# Power.net
KiCad netlist of a schematic drawn in Altium Designer
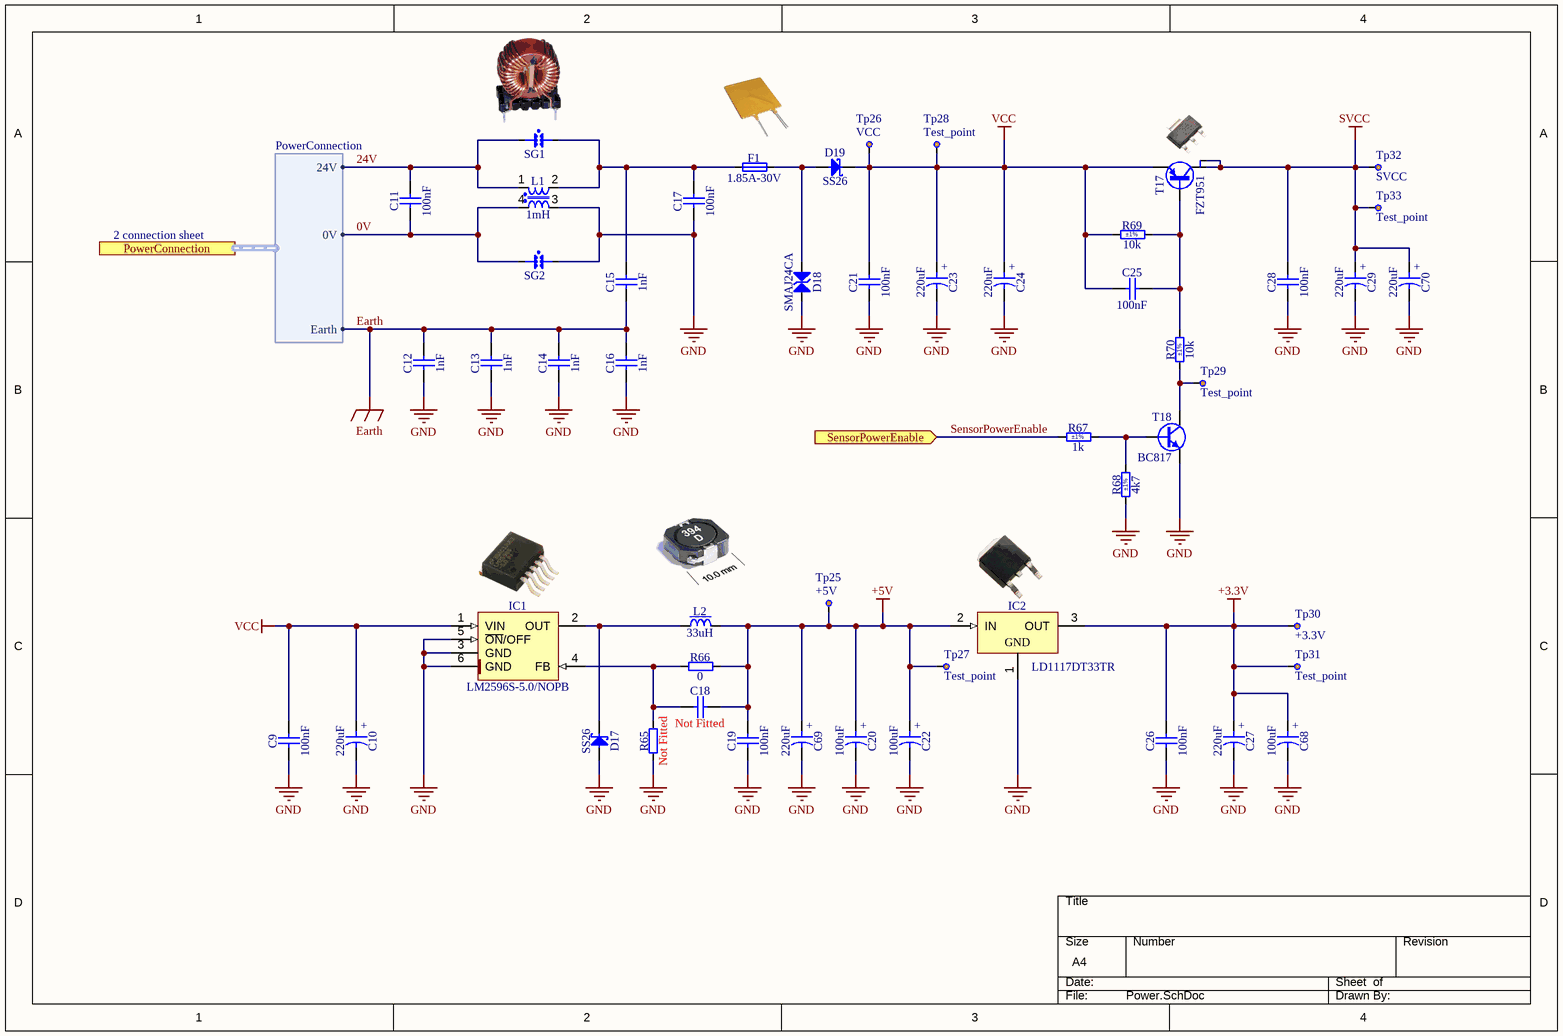
[diagram p0: Power.SchDoc]

(export (version "E")
  (design (tool "Eeschema 10.0.6"))
  (components
    (comp (ref "C9")
      (value "100nF")
      (footprint "CAPC3216X140N")
      (description "Non-polarised capacitor")
      (fields
        (field (name "PART NUMBER") "CC1206_100NF_100V_10%_X7R")
        (field (name "VOLTAGE") "100V")
        (field (name "AUTHOR") "CERN DEM JLC")
      )
      (libsource (lib "Capacitors") (part "Capacitor - non polarized"))
    )
    (comp (ref "C10")
      (value "220uF")
      (footprint "CAPAE830X1020N")
      (description "Polarised capacitor")
      (fields
        (field (name "PART NUMBER") "CAE830-1020_220UF_50V_20%")
        (field (name "VOLTAGE") "50V")
        (field (name "AUTHOR") "CERN DEM BC")
      )
      (libsource (lib "Capacitors") (part "Capacitor - polarized"))
    )
    (comp (ref "C11")
      (value "100nF")
      (footprint "CAPC3216X140N")
      (description "Non-polarised capacitor")
      (fields
        (field (name "PART NUMBER") "CC1206_100NF_100V_10%_X7R")
        (field (name "VOLTAGE") "100V")
        (field (name "AUTHOR") "CERN DEM JLC")
      )
      (libsource (lib "Capacitors") (part "Capacitor - non polarized"))
    )
    (comp (ref "C12")
      (value "1nF")
      (footprint "CAPC3216X94N")
      (description "Non-polarised capacitor")
      (fields
        (field (name "PART NUMBER") "CC1206_1NF_200V_10%_X7R")
        (field (name "VOLTAGE") "200V")
        (field (name "AUTHOR") "CERN DEM JLC")
      )
      (libsource (lib "Capacitors") (part "Capacitor - non polarized"))
    )
    (comp (ref "C13")
      (value "1nF")
      (footprint "CAPC3216X94N")
      (description "Non-polarised capacitor")
      (fields
        (field (name "PART NUMBER") "CC1206_1NF_200V_10%_X7R")
        (field (name "VOLTAGE") "200V")
        (field (name "AUTHOR") "CERN DEM JLC")
      )
      (libsource (lib "Capacitors") (part "Capacitor - non polarized"))
    )
    (comp (ref "C14")
      (value "1nF")
      (footprint "CAPC3216X94N")
      (description "Non-polarised capacitor")
      (fields
        (field (name "PART NUMBER") "CC1206_1NF_200V_10%_X7R")
        (field (name "VOLTAGE") "200V")
        (field (name "AUTHOR") "CERN DEM JLC")
      )
      (libsource (lib "Capacitors") (part "Capacitor - non polarized"))
    )
    (comp (ref "C15")
      (value "1nF")
      (footprint "CAPC3216X94N")
      (description "Non-polarised capacitor")
      (fields
        (field (name "PART NUMBER") "CC1206_1NF_200V_10%_X7R")
        (field (name "VOLTAGE") "200V")
        (field (name "AUTHOR") "CERN DEM JLC")
      )
      (libsource (lib "Capacitors") (part "Capacitor - non polarized"))
    )
    (comp (ref "C16")
      (value "1nF")
      (footprint "CAPC3216X94N")
      (description "Non-polarised capacitor")
      (fields
        (field (name "PART NUMBER") "CC1206_1NF_200V_10%_X7R")
        (field (name "VOLTAGE") "200V")
        (field (name "AUTHOR") "CERN DEM JLC")
      )
      (libsource (lib "Capacitors") (part "Capacitor - non polarized"))
    )
    (comp (ref "C17")
      (value "100nF")
      (footprint "CAPC3216X140N")
      (description "Non-polarised capacitor")
      (fields
        (field (name "PART NUMBER") "CC1206_100NF_100V_10%_X7R")
        (field (name "VOLTAGE") "100V")
        (field (name "AUTHOR") "CERN DEM JLC")
      )
      (libsource (lib "Capacitors") (part "Capacitor - non polarized"))
    )
    (comp (ref "C18")
      (value "Not Fitted")
      (footprint "CAPC2012X135N")
      (description "Non-polarised capacitor")
      (fields
        (field (name "PART NUMBER") "CC0805_NO-VALUE")
        (field (name "MANUFACTURER") "Undefined")
        (field (name "AUTHOR") "CERN DEM JLC")
      )
      (libsource (lib "Capacitors") (part "Capacitor - non polarized"))
    )
    (comp (ref "C19")
      (value "100nF")
      (footprint "CAPC1608X87N")
      (description "Non-polarised capacitor")
      (fields
        (field (name "PART NUMBER") "CC0603_100NF_50V_10%_X7R")
        (field (name "VOLTAGE") "50V")
        (field (name "AUTHOR") "CERN DEM JLC")
      )
      (libsource (lib "Capacitors") (part "Capacitor - non polarized"))
    )
    (comp (ref "C20")
      (value "100uF")
      (footprint "CAPMP6032X280N")
      (description "Polarised capacitor")
      (fields
        (field (name "PART NUMBER") "CTE6032-28_100UF_16V_10%")
        (field (name "VOLTAGE") "16V")
        (field (name "AUTHOR") "CERN DEM JLC")
      )
      (libsource (lib "Capacitors") (part "Capacitor - polarized"))
    )
    (comp (ref "C21")
      (value "100nF")
      (footprint "CAPC3216X140N")
      (description "Non-polarised capacitor")
      (fields
        (field (name "PART NUMBER") "CC1206_100NF_100V_10%_X7R")
        (field (name "VOLTAGE") "100V")
        (field (name "AUTHOR") "CERN DEM JLC")
      )
      (libsource (lib "Capacitors") (part "Capacitor - non polarized"))
    )
    (comp (ref "C22")
      (value "100uF")
      (footprint "CAPMP6032X280N")
      (description "Polarised capacitor")
      (fields
        (field (name "PART NUMBER") "CTE6032-28_100UF_16V_10%")
        (field (name "VOLTAGE") "16V")
        (field (name "AUTHOR") "CERN DEM JLC")
      )
      (libsource (lib "Capacitors") (part "Capacitor - polarized"))
    )
    (comp (ref "C23")
      (value "220uF")
      (footprint "CAPAE830X1020N")
      (description "Polarised capacitor")
      (fields
        (field (name "PART NUMBER") "CAE830-1020_220UF_50V_20%")
        (field (name "VOLTAGE") "50V")
        (field (name "AUTHOR") "CERN DEM BC")
      )
      (libsource (lib "Capacitors") (part "Capacitor - polarized"))
    )
    (comp (ref "C24")
      (value "220uF")
      (footprint "CAPAE830X1020N")
      (description "Polarised capacitor")
      (fields
        (field (name "PART NUMBER") "CAE830-1020_220UF_50V_20%")
        (field (name "VOLTAGE") "50V")
        (field (name "AUTHOR") "CERN DEM BC")
      )
      (libsource (lib "Capacitors") (part "Capacitor - polarized"))
    )
    (comp (ref "C25")
      (value "100nF")
      (footprint "CAPC3216X140N")
      (description "Non-polarised capacitor")
      (fields
        (field (name "PART NUMBER") "CC1206_100NF_100V_10%_X7R")
        (field (name "VOLTAGE") "100V")
        (field (name "AUTHOR") "CERN DEM JLC")
      )
      (libsource (lib "Capacitors") (part "Capacitor - non polarized"))
    )
    (comp (ref "C26")
      (value "100nF")
      (footprint "CAPC1608X87N")
      (description "Non-polarised capacitor")
      (fields
        (field (name "PART NUMBER") "CC0603_100NF_50V_10%_X7R")
        (field (name "VOLTAGE") "50V")
        (field (name "AUTHOR") "CERN DEM JLC")
      )
      (libsource (lib "Capacitors") (part "Capacitor - non polarized"))
    )
    (comp (ref "C27")
      (value "220uF")
      (footprint "CAPAE830X1020N")
      (description "Polarised capacitor")
      (fields
        (field (name "PART NUMBER") "CAE830-1020_220UF_50V_20%")
        (field (name "VOLTAGE") "50V")
        (field (name "AUTHOR") "CERN DEM BC")
      )
      (libsource (lib "Capacitors") (part "Capacitor - polarized"))
    )
    (comp (ref "C28")
      (value "100nF")
      (footprint "CAPC3216X140N")
      (description "Non-polarised capacitor")
      (fields
        (field (name "PART NUMBER") "CC1206_100NF_100V_10%_X7R")
        (field (name "VOLTAGE") "100V")
        (field (name "AUTHOR") "CERN DEM JLC")
      )
      (libsource (lib "Capacitors") (part "Capacitor - non polarized"))
    )
    (comp (ref "C29")
      (value "220uF")
      (footprint "CAPAE830X1020N")
      (description "Polarised capacitor")
      (fields
        (field (name "PART NUMBER") "CAE830-1020_220UF_50V_20%")
        (field (name "VOLTAGE") "50V")
        (field (name "AUTHOR") "CERN DEM BC")
      )
      (libsource (lib "Capacitors") (part "Capacitor - polarized"))
    )
    (comp (ref "C68")
      (value "100uF")
      (footprint "CAPMP6032X280N")
      (description "Polarised capacitor")
      (fields
        (field (name "PART NUMBER") "CTE6032-28_100UF_16V_10%")
        (field (name "VOLTAGE") "16V")
        (field (name "AUTHOR") "CERN DEM JLC")
      )
      (libsource (lib "Capacitors") (part "Capacitor - polarized"))
    )
    (comp (ref "C69")
      (value "220uF")
      (footprint "CAPAE830X1020N")
      (description "Polarised capacitor")
      (fields
        (field (name "PART NUMBER") "CAE830-1020_220UF_50V_20%")
        (field (name "VOLTAGE") "50V")
        (field (name "AUTHOR") "CERN DEM BC")
      )
      (libsource (lib "Capacitors") (part "Capacitor - polarized"))
    )
    (comp (ref "C70")
      (value "220uF")
      (footprint "CAPAE830X1020N")
      (description "Polarised capacitor")
      (fields
        (field (name "PART NUMBER") "CAE830-1020_220UF_50V_20%")
        (field (name "VOLTAGE") "50V")
        (field (name "AUTHOR") "CERN DEM BC")
      )
      (libsource (lib "Capacitors") (part "Capacitor - polarized"))
    )
    (comp (ref "D17")
      (value "SS26")
      (footprint "DIOM5336X265N")
      (description "Schottky Diode")
      (fields
        (field (name "VOLTAGE") "60V")
        (field (name "POWER") "2A")
        (field (name "AUTHOR") "CERN DEM JMW")
      )
      (libsource (lib "ICs And Semiconductors") (part "Diode Schottky"))
    )
    (comp (ref "D18")
      (value "SMAJ24CA")
      (footprint "DIOM5226X262N")
      (description "Transient Voltage Suppressor Diode (Bi-Directional)")
      (fields
        (field (name "VOLTAGE") "24V")
        (field (name "POWER") "400W")
        (field (name "AUTHOR") "CERN DEM JLC")
      )
      (libsource (lib "ICs And Semiconductors") (part "Diode TVS Bi-Directional"))
    )
    (comp (ref "D19")
      (value "SS26")
      (footprint "DIOM5336X265N")
      (description "Schottky Diode")
      (fields
        (field (name "VOLTAGE") "60V")
        (field (name "POWER") "2A")
        (field (name "AUTHOR") "CERN DEM JMW")
      )
      (libsource (lib "ICs And Semiconductors") (part "Diode Schottky"))
    )
    (comp (ref "F1")
      (value "1.85A-30V")
      (footprint "FUSR_LITTELFUSE_RUEF185")
      (description "Fuse")
      (fields
        (field (name "PART NUMBER") "FUSR_LITTELFUSE_RUEF185")
        (field (name "MANUFACTURER") "LITTELFUSE")
        (field (name "AUTHOR") "CERN DEM BC")
      )
      (libsource (lib "Eletro-mechanical") (part "Fuse"))
    )
    (comp (ref "IC1")
      (value "LM2596S-5.0/NOPB")
      (footprint "TO170P1435X465-6N-R1041X635")
      (description "SIMPLE SWITCHER® Power Converter 150kHz, 3A Step-Down Voltage Regulator")
      (fields (field (name "MANUFACTURER") "TEXAS INSTRUMENTS") (field (name "AUTHOR") "CERN DEM JLC"))
      (libsource (lib "ICs And Semiconductors") (part "LM2596"))
    )
    (comp (ref "IC2")
      (value "LD1117DT33TR")
      (footprint "TO228P972X240-3N-R540X510")
      (description "3-Terminal Regulator 1=GND 2=IN 3=OUT")
      (fields (field (name "MANUFACTURER") "ST MICROELECTRONICS") (field (name "AUTHOR") "CERN DEM JLC"))
      (libsource (lib "ICs And Semiconductors") (part "REG3 1GND-2IN-3OUT"))
    )
    (comp (ref "L1")
      (value "1mH")
      (footprint "IND_WURTH_WE-CMB-XS")
      (description "Inductor Common Mode")
      (fields
        (field (name "PART NUMBER") "IND_1MH_30%_WURTH_WE-CMB-XS")
        (field (name "POWER") "2A")
        (field (name "AUTHOR") "CERN DEM JLC")
      )
      (libsource (lib "Inductors & Transformers") (part "Inductor Common Mode 1Dot-2 4Dot-3"))
    )
    (comp (ref "L2")
      (value "33uH")
      (footprint "IND_COILCRAFT_MSS1038")
      (description "Inductor With Core")
      (fields
        (field (name "PART NUMBER") "IND_33UH_20%_COILCRAFT_MSS1038")
        (field (name "POWER") "1.6A")
        (field (name "AUTHOR") "CERN DEM JLC")
      )
      (libsource (lib "Inductors & Transformers") (part "Inductor With Magnetic core"))
    )
    (comp (ref "R65")
      (value "Not Fitted")
      (footprint "RESC2012X60N")
      (description "Resistor")
      (fields
        (field (name "PART NUMBER") "R0805_NO-VALUE")
        (field (name "MANUFACTURER") "Undefined")
        (field (name "AUTHOR") "CERN DEM JLC")
      )
      (libsource (lib "Resistors") (part "Resistor"))
    )
    (comp (ref "R66")
      (value "0")
      (footprint "RESC1608X55N")
      (description "Resistor")
      (fields
        (field (name "PART NUMBER") "R0603_0R_JUMPER")
        (field (name "MANUFACTURER") "GENERIC")
        (field (name "AUTHOR") "CERN DEM JLC")
      )
      (libsource (lib "Resistors") (part "Resistor"))
    )
    (comp (ref "R67")
      (value "1k")
      (footprint "RESC1608X55N")
      (description "Resistor - 1%")
      (fields
        (field (name "TOLERANCE") "±1%")
        (field (name "PART NUMBER") "R0603_1K_1%_0.1W_100PPM")
        (field (name "POWER") "0.1W")
        (field (name "AUTHOR") "CERN DEM JLC")
      )
      (libsource (lib "Resistors") (part "Resistor - 1%"))
    )
    (comp (ref "R68")
      (value "4k7")
      (footprint "RESC1608X55N")
      (description "Resistor - 1%")
      (fields
        (field (name "TOLERANCE") "±1%")
        (field (name "PART NUMBER") "R0603_4K7_1%_0.1W_100PPM")
        (field (name "POWER") "0.1W")
        (field (name "AUTHOR") "CERN DEM JLC")
      )
      (libsource (lib "Resistors") (part "Resistor - 1%"))
    )
    (comp (ref "R69")
      (value "10k")
      (footprint "RESC3216X65N")
      (description "Resistor - 1%")
      (fields
        (field (name "TOLERANCE") "±1%")
        (field (name "PART NUMBER") "R1206_10K_1%_0.25W_100PPM")
        (field (name "POWER") "0.25W")
        (field (name "AUTHOR") "CERN DEM JLC")
      )
      (libsource (lib "Resistors") (part "Resistor - 1%"))
    )
    (comp (ref "R70")
      (value "10k")
      (footprint "RESC3216X65N")
      (description "Resistor - 1%")
      (fields
        (field (name "TOLERANCE") "±1%")
        (field (name "PART NUMBER") "R1206_10K_1%_0.25W_100PPM")
        (field (name "POWER") "0.25W")
        (field (name "AUTHOR") "CERN DEM JLC")
      )
      (libsource (lib "Resistors") (part "Resistor - 1%"))
    )
    (comp (ref "SG1")
      (value "Spark Gap")
      (footprint "SparkGap:PCB_SPARK_GAP")
      (description "PCB Spark Gap")
      (libsource (lib "SparkGap") (part "SparkGap"))
    )
    (comp (ref "SG2")
      (value "Spark Gap")
      (footprint "SparkGap:PCB_SPARK_GAP")
      (description "PCB Spark Gap")
      (libsource (lib "SparkGap") (part "SparkGap"))
    )
    (comp (ref "T17")
      (value "FZT951")
      (footprint "SOT230P700X180-4N")
      (description "PNP Transistor")
      (fields (field (name "MANUFACTURER") "ZETEX SEMICONDUCTORS") (field (name "AUTHOR") "CERN DEM JLC"))
      (libsource (lib "ICs And Semiconductors") (part "PNP B1 C2 E3 C4"))
    )
    (comp (ref "T18")
      (value "BC817")
      (footprint "SOT95P230X110-3N")
      (description "NPN Transistor")
      (fields (field (name "MANUFACTURER") "NXP SEMICONDUCTORS") (field (name "AUTHOR") "CERN DEM JLC"))
      (libsource (lib "ICs And Semiconductors") (part "NPN B1 E2 C3"))
    )
    (comp (ref "Tp25")
      (value "+5V")
      (footprint "fromST:TP_C40")
      (description "Test point")
      (fields (field (name "PUBLISHER") "Altium Limited"))
      (libsource (lib "Sajad_Altium_Library") (part "Test point"))
    )
    (comp (ref "Tp26")
      (value "VCC")
      (footprint "fromST:TP_C40")
      (description "Test point")
      (fields (field (name "PUBLISHER") "Altium Limited"))
      (libsource (lib "Sajad_Altium_Library") (part "Test point"))
    )
    (comp (ref "Tp27")
      (value "Test_point")
      (footprint "fromST:TP_C40")
      (description "Test point")
      (fields (field (name "PUBLISHER") "Altium Limited"))
      (libsource (lib "Sajad_Altium_Library") (part "Test point"))
    )
    (comp (ref "Tp28")
      (value "Test_point")
      (footprint "fromST:TP_C40")
      (description "Test point")
      (fields (field (name "PUBLISHER") "Altium Limited"))
      (libsource (lib "Sajad_Altium_Library") (part "Test point"))
    )
    (comp (ref "Tp29")
      (value "Test_point")
      (footprint "fromST:TP_C40")
      (description "Test point")
      (fields (field (name "PUBLISHER") "Altium Limited"))
      (libsource (lib "Sajad_Altium_Library") (part "Test point"))
    )
    (comp (ref "Tp30")
      (value "+3.3V")
      (footprint "fromST:TP_C40")
      (description "Test point")
      (fields (field (name "PUBLISHER") "Altium Limited"))
      (libsource (lib "Sajad_Altium_Library") (part "Test point"))
    )
    (comp (ref "Tp31")
      (value "Test_point")
      (footprint "fromST:TP_C40")
      (description "Test point")
      (fields (field (name "PUBLISHER") "Altium Limited"))
      (libsource (lib "Sajad_Altium_Library") (part "Test point"))
    )
    (comp (ref "Tp32")
      (value "SVCC")
      (footprint "fromST:TP_C40")
      (description "Test point")
      (fields (field (name "PUBLISHER") "Altium Limited"))
      (libsource (lib "Sajad_Altium_Library") (part "Test point"))
    )
    (comp (ref "Tp33")
      (value "Test_point")
      (footprint "fromST:TP_C40")
      (description "Test point")
      (fields (field (name "PUBLISHER") "Altium Limited"))
      (libsource (lib "Sajad_Altium_Library") (part "Test point"))
    )
  )
  (nets
    (net (code "2") (name "+3.3V") (class "Default")
      (node (ref "C26") (pin "2") (pinfunction "2_2") (pintype "passive"))
      (node (ref "C27") (pin "1") (pinfunction "1_1") (pintype "passive"))
      (node (ref "C68") (pin "1") (pinfunction "1_1") (pintype "passive"))
      (node (ref "IC2") (pin "3") (pinfunction "OUT_3") (pintype "power_in"))
      (node (ref "Tp30") (pin "1") (pinfunction "1_1") (pintype "passive"))
      (node (ref "Tp31") (pin "1") (pinfunction "1_1") (pintype "passive"))
    )
    (net (code "3") (name "+5V") (class "Default")
      (node (ref "C18") (pin "2") (pinfunction "2_2") (pintype "passive"))
      (node (ref "C19") (pin "2") (pinfunction "2_2") (pintype "passive"))
      (node (ref "C20") (pin "1") (pinfunction "1_1") (pintype "passive"))
      (node (ref "C22") (pin "1") (pinfunction "1_1") (pintype "passive"))
      (node (ref "C69") (pin "1") (pinfunction "1_1") (pintype "passive"))
      (node (ref "IC2") (pin "2") (pinfunction "IN_2") (pintype "input"))
      (node (ref "L2") (pin "2") (pinfunction "2_2") (pintype "passive"))
      (node (ref "R66") (pin "2") (pinfunction "2_2") (pintype "passive"))
      (node (ref "Tp25") (pin "1") (pinfunction "1_1") (pintype "passive"))
      (node (ref "Tp27") (pin "1") (pinfunction "1_1") (pintype "passive"))
    )
    (net (code "4") (name "/0V") (class "Default")
      (node (ref "C11") (pin "1") (pinfunction "1_1") (pintype "passive"))
      (node (ref "L1") (pin "4") (pinfunction "4_4") (pintype "passive"))
      (node (ref "SG2") (pin "1") (pintype "passive"))
    )
    (net (code "5") (name "/24V") (class "Default")
      (node (ref "C11") (pin "2") (pinfunction "2_2") (pintype "passive"))
      (node (ref "L1") (pin "1") (pinfunction "1_1") (pintype "passive"))
      (node (ref "SG1") (pin "1") (pintype "passive"))
    )
    (net (code "6") (name "/SensorPowerEnable") (class "Default")
      (node (ref "R67") (pin "1") (pinfunction "1_1") (pintype "passive"))
    )
    (net (code "8") (name "Earth") (class "Default")
      (node (ref "C12") (pin "2") (pinfunction "2_2") (pintype "passive"))
      (node (ref "C13") (pin "2") (pinfunction "2_2") (pintype "passive"))
      (node (ref "C14") (pin "2") (pinfunction "2_2") (pintype "passive"))
      (node (ref "C15") (pin "1") (pinfunction "1_1") (pintype "passive"))
      (node (ref "C16") (pin "2") (pinfunction "2_2") (pintype "passive"))
    )
    (net (code "9") (name "GND") (class "Default")
      (node (ref "C10") (pin "2") (pinfunction "2_2") (pintype "passive"))
      (node (ref "C12") (pin "1") (pinfunction "1_1") (pintype "passive"))
      (node (ref "C13") (pin "1") (pinfunction "1_1") (pintype "passive"))
      (node (ref "C14") (pin "1") (pinfunction "1_1") (pintype "passive"))
      (node (ref "C16") (pin "1") (pinfunction "1_1") (pintype "passive"))
      (node (ref "C17") (pin "1") (pinfunction "1_1") (pintype "passive"))
      (node (ref "C19") (pin "1") (pinfunction "1_1") (pintype "passive"))
      (node (ref "C20") (pin "2") (pinfunction "2_2") (pintype "passive"))
      (node (ref "C21") (pin "1") (pinfunction "1_1") (pintype "passive"))
      (node (ref "C22") (pin "2") (pinfunction "2_2") (pintype "passive"))
      (node (ref "C23") (pin "2") (pinfunction "2_2") (pintype "passive"))
      (node (ref "C24") (pin "2") (pinfunction "2_2") (pintype "passive"))
      (node (ref "C26") (pin "1") (pinfunction "1_1") (pintype "passive"))
      (node (ref "C27") (pin "2") (pinfunction "2_2") (pintype "passive"))
      (node (ref "C28") (pin "1") (pinfunction "1_1") (pintype "passive"))
      (node (ref "C29") (pin "2") (pinfunction "2_2") (pintype "passive"))
      (node (ref "C68") (pin "2") (pinfunction "2_2") (pintype "passive"))
      (node (ref "C69") (pin "2") (pinfunction "2_2") (pintype "passive"))
      (node (ref "C70") (pin "2") (pinfunction "2_2") (pintype "passive"))
      (node (ref "C9") (pin "1") (pinfunction "1_1") (pintype "passive"))
      (node (ref "D17") (pin "2") (pinfunction "A_2") (pintype "passive"))
      (node (ref "D18") (pin "2") (pinfunction "2_2") (pintype "passive"))
      (node (ref "IC1") (pin "3") (pinfunction "GND_3") (pintype "power_in"))
      (node (ref "IC1") (pin "5") (pinfunction "~{ON}/OFF_5") (pintype "input"))
      (node (ref "IC1") (pin "6") (pinfunction "GND_6") (pintype "power_in"))
      (node (ref "IC2") (pin "1") (pinfunction "GND_1") (pintype "power_in"))
      (node (ref "L1") (pin "3") (pinfunction "3_3") (pintype "passive"))
      (node (ref "R65") (pin "1") (pinfunction "1_1") (pintype "passive"))
      (node (ref "R68") (pin "1") (pinfunction "1_1") (pintype "passive"))
      (node (ref "SG2") (pin "2") (pintype "passive"))
      (node (ref "T18") (pin "2") (pinfunction "E_2") (pintype "passive"))
    )
    (net (code "10") (name "Net-(C15-Pad2)") (class "Default")
      (node (ref "C15") (pin "2") (pinfunction "2_2") (pintype "passive"))
      (node (ref "C17") (pin "2") (pinfunction "2_2") (pintype "passive"))
      (node (ref "F1") (pin "1") (pinfunction "1_1") (pintype "passive"))
      (node (ref "L1") (pin "2") (pinfunction "2_2") (pintype "passive"))
      (node (ref "SG1") (pin "2") (pintype "passive"))
    )
    (net (code "11") (name "Net-(D17-C)") (class "Default")
      (node (ref "D17") (pin "1") (pinfunction "C_1") (pintype "passive"))
      (node (ref "IC1") (pin "2") (pinfunction "OUT_2") (pintype "power_in"))
      (node (ref "L2") (pin "1") (pinfunction "1_1") (pintype "passive"))
    )
    (net (code "12") (name "Net-(D19-A)") (class "Default")
      (node (ref "D18") (pin "1") (pinfunction "1_1") (pintype "passive"))
      (node (ref "D19") (pin "2") (pinfunction "A_2") (pintype "passive"))
      (node (ref "F1") (pin "2") (pinfunction "2_2") (pintype "passive"))
    )
    (net (code "13") (name "Net-(IC1-FB)") (class "Default")
      (node (ref "C18") (pin "1") (pinfunction "1_1") (pintype "passive"))
      (node (ref "IC1") (pin "4") (pinfunction "FB_4") (pintype "input"))
      (node (ref "R65") (pin "2") (pinfunction "2_2") (pintype "passive"))
      (node (ref "R66") (pin "1") (pinfunction "1_1") (pintype "passive"))
    )
    (net (code "14") (name "Net-(T17-B)") (class "Default")
      (node (ref "C25") (pin "2") (pinfunction "2_2") (pintype "passive"))
      (node (ref "R69") (pin "2") (pinfunction "2_2") (pintype "passive"))
      (node (ref "R70") (pin "2") (pinfunction "2_2") (pintype "passive"))
      (node (ref "T17") (pin "1") (pinfunction "B_1") (pintype "passive"))
    )
    (net (code "15") (name "Net-(T18-B)") (class "Default")
      (node (ref "R67") (pin "2") (pinfunction "2_2") (pintype "passive"))
      (node (ref "R68") (pin "2") (pinfunction "2_2") (pintype "passive"))
      (node (ref "T18") (pin "1") (pinfunction "B_1") (pintype "passive"))
    )
    (net (code "16") (name "Net-(T18-C)") (class "Default")
      (node (ref "R70") (pin "1") (pinfunction "1_1") (pintype "passive"))
      (node (ref "T18") (pin "3") (pinfunction "C_3") (pintype "passive"))
      (node (ref "Tp29") (pin "1") (pinfunction "1_1") (pintype "passive"))
    )
    (net (code "17") (name "SVCC") (class "Default")
      (node (ref "C28") (pin "2") (pinfunction "2_2") (pintype "passive"))
      (node (ref "C29") (pin "1") (pinfunction "1_1") (pintype "passive"))
      (node (ref "C70") (pin "1") (pinfunction "1_1") (pintype "passive"))
      (node (ref "T17") (pin "2") (pinfunction "C_2") (pintype "passive"))
      (node (ref "T17") (pin "4") (pinfunction "C_4") (pintype "passive"))
      (node (ref "Tp32") (pin "1") (pinfunction "1_1") (pintype "passive"))
      (node (ref "Tp33") (pin "1") (pinfunction "1_1") (pintype "passive"))
    )
    (net (code "18") (name "VCC") (class "Default")
      (node (ref "C10") (pin "1") (pinfunction "1_1") (pintype "passive"))
      (node (ref "C21") (pin "2") (pinfunction "2_2") (pintype "passive"))
      (node (ref "C23") (pin "1") (pinfunction "1_1") (pintype "passive"))
      (node (ref "C24") (pin "1") (pinfunction "1_1") (pintype "passive"))
      (node (ref "C25") (pin "1") (pinfunction "1_1") (pintype "passive"))
      (node (ref "C9") (pin "2") (pinfunction "2_2") (pintype "passive"))
      (node (ref "D19") (pin "1") (pinfunction "C_1") (pintype "passive"))
      (node (ref "IC1") (pin "1") (pinfunction "VIN_1") (pintype "input"))
      (node (ref "R69") (pin "1") (pinfunction "1_1") (pintype "passive"))
      (node (ref "T17") (pin "3") (pinfunction "E_3") (pintype "passive"))
      (node (ref "Tp26") (pin "1") (pinfunction "1_1") (pintype "passive"))
      (node (ref "Tp28") (pin "1") (pinfunction "1_1") (pintype "passive"))
    )
  )
)
